# PCB_PUMP_LED_SENSOR.net
KiCad netlist of a schematic drawn in EAGLE
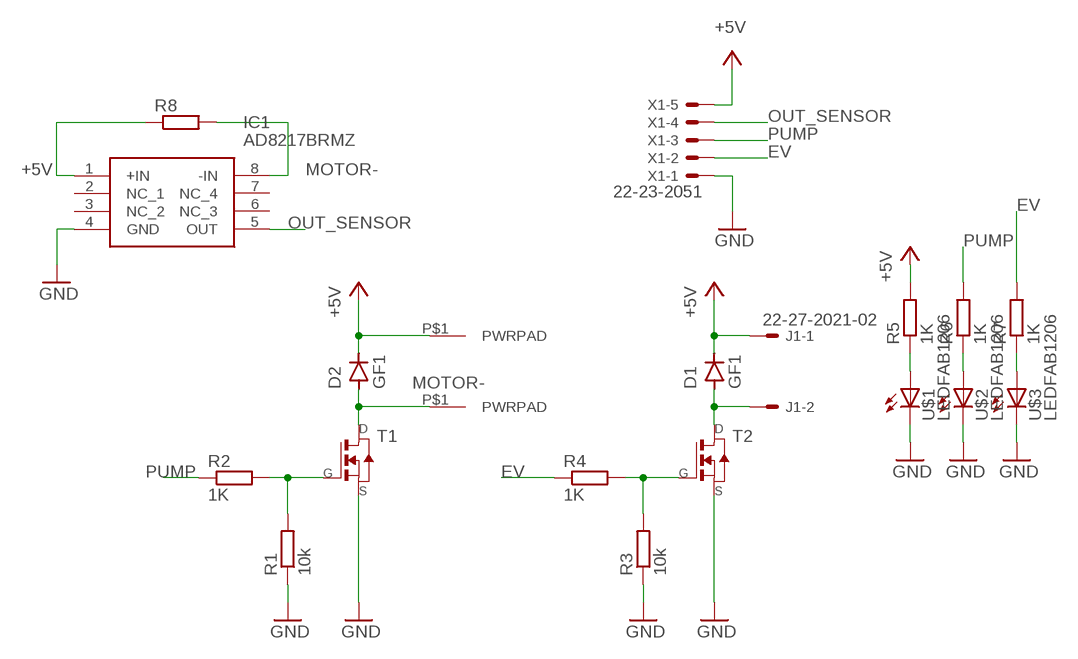
[diagram p0: schematic, sheet 1]

(export (version "E")
  (design (tool "Eeschema 10.0.6"))
  (components
    (comp (ref "D1")
      (value "GF1")
      (footprint "eagle-import:SMA-DO214AC")
      (libsource (lib "eagle-import") (part "GF1"))
    )
    (comp (ref "D2")
      (value "GF1")
      (footprint "eagle-import:SMA-DO214AC")
      (libsource (lib "eagle-import") (part "GF1"))
    )
    (comp (ref "IC1")
      (value "AD8217BRMZ")
      (footprint "eagle-import:SOP65P490X110-8N")
      (fields (field (name "MOUSER_PART_NUMBER") "584-AD8217BRMZ"))
      (libsource (lib "eagle-import") (part "AD8217BRMZ"))
    )
    (comp (ref "J1")
      (value "22-27-2021-02")
      (footprint "eagle-import:6410-02")
      (fields (field (name "MF") "MOLEX"))
      (libsource (lib "eagle-import") (part "22-?-0227-2021"))
    )
    (comp (ref "J3")
      (value "PWRPAD2-5MM")
      (footprint "eagle-import:PWRPAD_2-5MM")
      (libsource (lib "eagle-import") (part "PWRPAD2-5MM"))
    )
    (comp (ref "J4")
      (value "PWRPAD2-5MM")
      (footprint "eagle-import:PWRPAD_2-5MM")
      (libsource (lib "eagle-import") (part "PWRPAD2-5MM"))
    )
    (comp (ref "R1")
      (value "10k")
      (footprint "eagle-import:R1206")
      (libsource (lib "eagle-import") (part "R-EU_R1206"))
    )
    (comp (ref "R2")
      (value "1K")
      (footprint "eagle-import:R1206")
      (libsource (lib "eagle-import") (part "R-EU_R1206"))
    )
    (comp (ref "R3")
      (value "10k")
      (footprint "eagle-import:R1206")
      (libsource (lib "eagle-import") (part "R-EU_R1206"))
    )
    (comp (ref "R4")
      (value "1K")
      (footprint "eagle-import:R1206")
      (libsource (lib "eagle-import") (part "R-EU_R1206"))
    )
    (comp (ref "R5")
      (value "1K")
      (footprint "eagle-import:R1206")
      (libsource (lib "eagle-import") (part "R-EU_R1206"))
    )
    (comp (ref "R6")
      (value "1K")
      (footprint "eagle-import:R1206")
      (libsource (lib "eagle-import") (part "R-EU_R1206"))
    )
    (comp (ref "R7")
      (value "1K")
      (footprint "eagle-import:R1206")
      (libsource (lib "eagle-import") (part "R-EU_R1206"))
    )
    (comp (ref "R8")
      (value "R-EU_R0805")
      (footprint "eagle-import:R0805")
      (libsource (lib "eagle-import") (part "R-EU_R0805"))
    )
    (comp (ref "T1")
      (value "NMOSFETSOT23")
      (footprint "eagle-import:SOT-23")
      (libsource (lib "eagle-import") (part "NMOSFETSOT23"))
    )
    (comp (ref "T2")
      (value "NMOSFETSOT23")
      (footprint "eagle-import:SOT-23")
      (libsource (lib "eagle-import") (part "NMOSFETSOT23"))
    )
    (comp (ref "U$1")
      (value "LEDFAB1206")
      (footprint "eagle-import:LED1206FAB")
      (libsource (lib "eagle-import") (part "LEDFAB1206"))
    )
    (comp (ref "U$2")
      (value "LEDFAB1206")
      (footprint "eagle-import:LED1206FAB")
      (libsource (lib "eagle-import") (part "LEDFAB1206"))
    )
    (comp (ref "U$3")
      (value "LEDFAB1206")
      (footprint "eagle-import:LED1206FAB")
      (libsource (lib "eagle-import") (part "LEDFAB1206"))
    )
    (comp (ref "X1")
      (value "22-23-2051")
      (footprint "eagle-import:22-23-2051")
      (fields (field (name "MF") "MOLEX"))
      (libsource (lib "eagle-import") (part "22-23-2051"))
    )
  )
  (nets
    (net (code "1") (name "+5V") (class "Default")
      (node (ref "D1") (pin "K") (pinfunction "C_K") (pintype "passive"))
      (node (ref "D2") (pin "K") (pinfunction "C_K") (pintype "passive"))
      (node (ref "IC1") (pin "1") (pinfunction "+IN_1") (pintype "bidirectional"))
      (node (ref "J1") (pin "1") (pinfunction "S_1") (pintype "passive"))
      (node (ref "J4") (pin "P$1") (pinfunction "PWRPAD_P$1") (pintype "bidirectional"))
      (node (ref "R5") (pin "2") (pinfunction "2_2") (pintype "passive"))
      (node (ref "R8") (pin "1") (pinfunction "1_1") (pintype "passive"))
      (node (ref "X1") (pin "5") (pinfunction "S_5") (pintype "passive"))
    )
    (net (code "2") (name "/EV") (class "Default")
      (node (ref "R4") (pin "1") (pinfunction "1_1") (pintype "passive"))
      (node (ref "R7") (pin "2") (pinfunction "2_2") (pintype "passive"))
      (node (ref "X1") (pin "2") (pinfunction "S_2") (pintype "passive"))
    )
    (net (code "3") (name "/MOTOR-") (class "Default")
      (node (ref "D2") (pin "A") (pinfunction "A_A") (pintype "passive"))
      (node (ref "IC1") (pin "8") (pinfunction "-IN_8") (pintype "bidirectional"))
      (node (ref "J3") (pin "P$1") (pinfunction "PWRPAD_P$1") (pintype "bidirectional"))
      (node (ref "R8") (pin "2") (pinfunction "2_2") (pintype "passive"))
      (node (ref "T1") (pin "1") (pinfunction "D_1") (pintype "passive"))
    )
    (net (code "4") (name "/OUT_SENSOR") (class "Default")
      (node (ref "IC1") (pin "5") (pinfunction "OUT_5") (pintype "bidirectional"))
      (node (ref "X1") (pin "4") (pinfunction "S_4") (pintype "passive"))
    )
    (net (code "5") (name "/PUMP") (class "Default")
      (node (ref "R2") (pin "1") (pinfunction "1_1") (pintype "passive"))
      (node (ref "R6") (pin "2") (pinfunction "2_2") (pintype "passive"))
      (node (ref "X1") (pin "3") (pinfunction "S_3") (pintype "passive"))
    )
    (net (code "6") (name "GND") (class "Default")
      (node (ref "IC1") (pin "4") (pinfunction "GND_4") (pintype "bidirectional"))
      (node (ref "R1") (pin "1") (pinfunction "1_1") (pintype "passive"))
      (node (ref "R3") (pin "1") (pinfunction "1_1") (pintype "passive"))
      (node (ref "T1") (pin "2") (pinfunction "S_2") (pintype "passive"))
      (node (ref "T2") (pin "2") (pinfunction "S_2") (pintype "passive"))
      (node (ref "U$1") (pin "2") (pinfunction "C_2") (pintype "passive"))
      (node (ref "U$2") (pin "2") (pinfunction "C_2") (pintype "passive"))
      (node (ref "U$3") (pin "2") (pinfunction "C_2") (pintype "passive"))
      (node (ref "X1") (pin "1") (pinfunction "S_1") (pintype "passive"))
    )
    (net (code "7") (name "Net-(J1B-S)") (class "Default")
      (node (ref "D1") (pin "A") (pinfunction "A_A") (pintype "passive"))
      (node (ref "J1") (pin "2") (pinfunction "S_2") (pintype "passive"))
      (node (ref "T2") (pin "1") (pinfunction "D_1") (pintype "passive"))
    )
    (net (code "8") (name "Net-(T1-G)") (class "Default")
      (node (ref "R1") (pin "2") (pinfunction "2_2") (pintype "passive"))
      (node (ref "R2") (pin "2") (pinfunction "2_2") (pintype "passive"))
      (node (ref "T1") (pin "3") (pinfunction "G_3") (pintype "passive"))
    )
    (net (code "9") (name "Net-(T2-G)") (class "Default")
      (node (ref "R3") (pin "2") (pinfunction "2_2") (pintype "passive"))
      (node (ref "R4") (pin "2") (pinfunction "2_2") (pintype "passive"))
      (node (ref "T2") (pin "3") (pinfunction "G_3") (pintype "passive"))
    )
    (net (code "10") (name "Net-(U$1-A)") (class "Default")
      (node (ref "R5") (pin "1") (pinfunction "1_1") (pintype "passive"))
      (node (ref "U$1") (pin "1") (pinfunction "A_1") (pintype "passive"))
    )
    (net (code "11") (name "Net-(U$2-A)") (class "Default")
      (node (ref "R6") (pin "1") (pinfunction "1_1") (pintype "passive"))
      (node (ref "U$2") (pin "1") (pinfunction "A_1") (pintype "passive"))
    )
    (net (code "12") (name "Net-(U$3-A)") (class "Default")
      (node (ref "R7") (pin "1") (pinfunction "1_1") (pintype "passive"))
      (node (ref "U$3") (pin "1") (pinfunction "A_1") (pintype "passive"))
    )
    (net (code "13") (name "unconnected-(IC1-NC_1-Pad2)") (class "Default")
      (node (ref "IC1") (pin "2") (pinfunction "NC_1_2") (pintype "bidirectional"))
    )
    (net (code "14") (name "unconnected-(IC1-NC_2-Pad3)") (class "Default")
      (node (ref "IC1") (pin "3") (pinfunction "NC_2_3") (pintype "bidirectional"))
    )
    (net (code "15") (name "unconnected-(IC1-NC_3-Pad6)") (class "Default")
      (node (ref "IC1") (pin "6") (pinfunction "NC_3_6") (pintype "bidirectional"))
    )
    (net (code "16") (name "unconnected-(IC1-NC_4-Pad7)") (class "Default")
      (node (ref "IC1") (pin "7") (pinfunction "NC_4_7") (pintype "bidirectional"))
    )
  )
)
